# shield_passage_vitesse.net
KiCad netlist of a schematic drawn in EAGLE
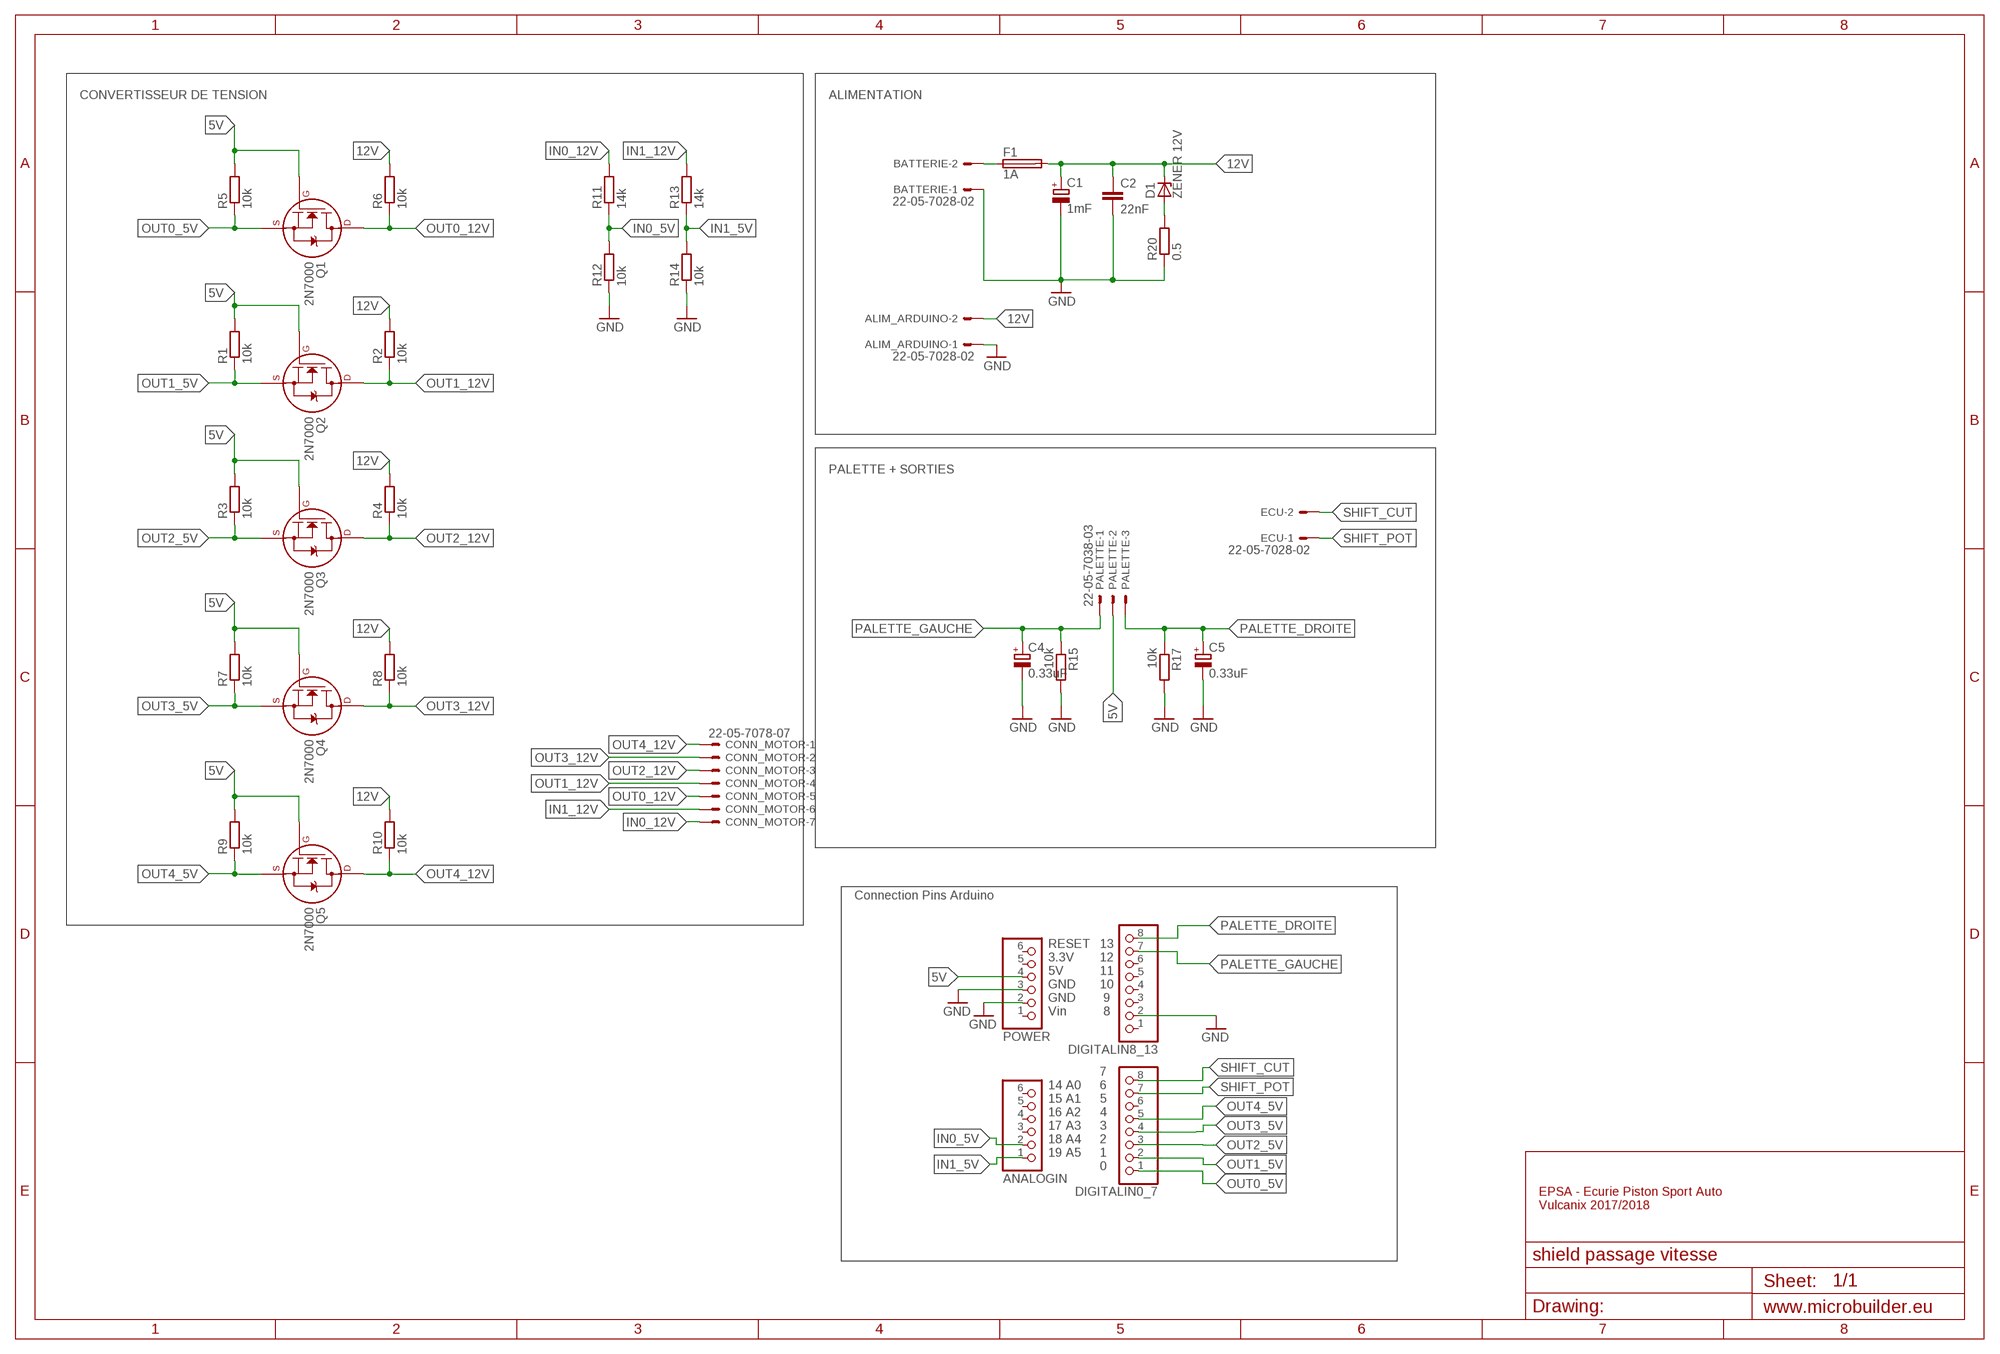
[diagram p0: schematic, sheet 1]

(export (version "E")
  (design (tool "Eeschema 10.0.6"))
  (components
    (comp (ref "ALIM_ARDUINO")
      (value "22-05-7028-02")
      (footprint "eagle-import:7395-02")
      (libsource (lib "eagle-import") (part "22-?-0205-7028"))
    )
    (comp (ref "ANALOGIN")
      (value "PINHD-1X6CB")
      (footprint "eagle-import:1X06-CLEANBIG")
      (libsource (lib "eagle-import") (part "PINHD-1X6CB"))
    )
    (comp (ref "BATTERIE")
      (value "22-05-7028-02")
      (footprint "eagle-import:7395-02")
      (libsource (lib "eagle-import") (part "22-?-0205-7028"))
    )
    (comp (ref "C1")
      (value "1mF")
      (footprint "eagle-import:E7,5-16")
      (libsource (lib "eagle-import") (part "rcl_334_CPOL-EUE7.5-16"))
    )
    (comp (ref "C2")
      (value "22nF")
      (footprint "eagle-import:C025-025X050")
      (libsource (lib "eagle-import") (part "C-EU025-025X050"))
    )
    (comp (ref "C4")
      (value "0.33uF")
      (footprint "eagle-import:E2,5-6E")
      (libsource (lib "eagle-import") (part "CPOL-EUE2,5-6E"))
    )
    (comp (ref "C5")
      (value "0.33uF")
      (footprint "eagle-import:E2,5-6E")
      (libsource (lib "eagle-import") (part "CPOL-EUE2,5-6E"))
    )
    (comp (ref "CONN_MOTOR")
      (value "22-05-7078-07")
      (footprint "eagle-import:7395-07")
      (libsource (lib "eagle-import") (part "22-?-0705-7078"))
    )
    (comp (ref "D1")
      (value "ZENER 12V")
      (footprint "eagle-import:DO41Z10")
      (libsource (lib "eagle-import") (part "ZENER-DIODEDO41Z10"))
    )
    (comp (ref "DIGITALIN0_7")
      (value "PINHD-1X8CLEANBIG")
      (footprint "eagle-import:1X08-CLEANBIG")
      (libsource (lib "eagle-import") (part "PINHD-1X8CLEANBIG"))
    )
    (comp (ref "DIGITALIN8_13")
      (value "PINHD-1X8CLEANBIG")
      (footprint "eagle-import:1X08-CLEANBIG")
      (libsource (lib "eagle-import") (part "PINHD-1X8CLEANBIG"))
    )
    (comp (ref "ECU")
      (value "22-05-7028-02")
      (footprint "eagle-import:7395-02")
      (libsource (lib "eagle-import") (part "22-?-0205-7028"))
    )
    (comp (ref "F1")
      (value "1A")
      (footprint "eagle-import:SH25")
      (fields (field (name "MF") "SCHURTER") (field (name "MPN") "0031.8211"))
      (libsource (lib "eagle-import") (part "SH25"))
    )
    (comp (ref "PALETTE")
      (value "22-05-7038-03")
      (footprint "eagle-import:7395-03")
      (libsource (lib "eagle-import") (part "22-?-0305-7038"))
    )
    (comp (ref "POWER")
      (value "PINHD-1X6CB")
      (footprint "eagle-import:1X06-CLEANBIG")
      (libsource (lib "eagle-import") (part "PINHD-1X6CB"))
    )
    (comp (ref "Q1")
      (value "2N7000")
      (footprint "eagle-import:TO-92")
      (libsource (lib "eagle-import") (part "2N700_TO920"))
    )
    (comp (ref "Q2")
      (value "2N7000")
      (footprint "eagle-import:TO-92")
      (libsource (lib "eagle-import") (part "2N700_TO920"))
    )
    (comp (ref "Q3")
      (value "2N7000")
      (footprint "eagle-import:TO-92")
      (libsource (lib "eagle-import") (part "2N700_TO920"))
    )
    (comp (ref "Q4")
      (value "2N7000")
      (footprint "eagle-import:TO-92")
      (libsource (lib "eagle-import") (part "2N700_TO920"))
    )
    (comp (ref "Q5")
      (value "2N7000")
      (footprint "eagle-import:TO-92")
      (libsource (lib "eagle-import") (part "2N700_TO920"))
    )
    (comp (ref "R1")
      (value "10k")
      (footprint "eagle-import:0204_7")
      (libsource (lib "eagle-import") (part "R-EU_0204/7"))
    )
    (comp (ref "R2")
      (value "10k")
      (footprint "eagle-import:0204_7")
      (libsource (lib "eagle-import") (part "R-EU_0204/7"))
    )
    (comp (ref "R3")
      (value "10k")
      (footprint "eagle-import:0204_7")
      (libsource (lib "eagle-import") (part "R-EU_0204/7"))
    )
    (comp (ref "R4")
      (value "10k")
      (footprint "eagle-import:0204_7")
      (libsource (lib "eagle-import") (part "R-EU_0204/7"))
    )
    (comp (ref "R5")
      (value "10k")
      (footprint "eagle-import:0204_7")
      (libsource (lib "eagle-import") (part "R-EU_0204/7"))
    )
    (comp (ref "R6")
      (value "10k")
      (footprint "eagle-import:0204_7")
      (libsource (lib "eagle-import") (part "R-EU_0204/7"))
    )
    (comp (ref "R7")
      (value "10k")
      (footprint "eagle-import:0204_7")
      (libsource (lib "eagle-import") (part "R-EU_0204/7"))
    )
    (comp (ref "R8")
      (value "10k")
      (footprint "eagle-import:0204_7")
      (libsource (lib "eagle-import") (part "R-EU_0204/7"))
    )
    (comp (ref "R9")
      (value "10k")
      (footprint "eagle-import:0204_7")
      (libsource (lib "eagle-import") (part "R-EU_0204/7"))
    )
    (comp (ref "R10")
      (value "10k")
      (footprint "eagle-import:0204_7")
      (libsource (lib "eagle-import") (part "R-EU_0204/7"))
    )
    (comp (ref "R11")
      (value "14k")
      (footprint "eagle-import:0204_7")
      (libsource (lib "eagle-import") (part "R-EU_0204/7"))
    )
    (comp (ref "R12")
      (value "10k")
      (footprint "eagle-import:0204_7")
      (libsource (lib "eagle-import") (part "R-EU_0204/7"))
    )
    (comp (ref "R13")
      (value "14k")
      (footprint "eagle-import:0204_7")
      (libsource (lib "eagle-import") (part "R-EU_0204/7"))
    )
    (comp (ref "R14")
      (value "10k")
      (footprint "eagle-import:0204_7")
      (libsource (lib "eagle-import") (part "R-EU_0204/7"))
    )
    (comp (ref "R15")
      (value "10k")
      (footprint "eagle-import:0204_7")
      (libsource (lib "eagle-import") (part "R-EU_0204/7"))
    )
    (comp (ref "R17")
      (value "10k")
      (footprint "eagle-import:0204_7")
      (libsource (lib "eagle-import") (part "R-EU_0204/7"))
    )
    (comp (ref "R20")
      (value "0.5")
      (footprint "eagle-import:0309_12")
      (libsource (lib "eagle-import") (part "R-EU_0309/12"))
    )
  )
  (nets
    (net (code "1") (name "5V") (class "Default")
      (node (ref "PALETTE") (pin "2") (pinfunction "S_2") (pintype "passive"))
      (node (ref "POWER") (pin "4") (pinfunction "4_4") (pintype "passive"))
      (node (ref "Q1") (pin "2") (pinfunction "G_2") (pintype "tri_state"))
      (node (ref "Q2") (pin "2") (pinfunction "G_2") (pintype "tri_state"))
      (node (ref "Q3") (pin "2") (pinfunction "G_2") (pintype "tri_state"))
      (node (ref "Q4") (pin "2") (pinfunction "G_2") (pintype "tri_state"))
      (node (ref "Q5") (pin "2") (pinfunction "G_2") (pintype "tri_state"))
      (node (ref "R1") (pin "2") (pinfunction "2_2") (pintype "passive"))
      (node (ref "R3") (pin "2") (pinfunction "2_2") (pintype "passive"))
      (node (ref "R5") (pin "2") (pinfunction "2_2") (pintype "passive"))
      (node (ref "R7") (pin "2") (pinfunction "2_2") (pintype "passive"))
      (node (ref "R9") (pin "2") (pinfunction "2_2") (pintype "passive"))
    )
    (net (code "2") (name "12V") (class "Default")
      (node (ref "ALIM_ARDUINO") (pin "2") (pinfunction "S_2") (pintype "passive"))
      (node (ref "C1") (pin "+") (pinfunction "+_+") (pintype "passive"))
      (node (ref "C2") (pin "1") (pinfunction "1_1") (pintype "passive"))
      (node (ref "D1") (pin "C") (pinfunction "C_C") (pintype "passive"))
      (node (ref "F1") (pin "2") (pinfunction "2_2") (pintype "passive"))
      (node (ref "R10") (pin "2") (pinfunction "2_2") (pintype "passive"))
      (node (ref "R2") (pin "2") (pinfunction "2_2") (pintype "passive"))
      (node (ref "R4") (pin "2") (pinfunction "2_2") (pintype "passive"))
      (node (ref "R6") (pin "2") (pinfunction "2_2") (pintype "passive"))
      (node (ref "R8") (pin "2") (pinfunction "2_2") (pintype "passive"))
    )
    (net (code "3") (name "GND") (class "Default")
      (node (ref "ALIM_ARDUINO") (pin "1") (pinfunction "S_1") (pintype "passive"))
      (node (ref "BATTERIE") (pin "1") (pinfunction "S_1") (pintype "passive"))
      (node (ref "C1") (pin "-") (pinfunction "-_-") (pintype "passive"))
      (node (ref "C2") (pin "2") (pinfunction "2_2") (pintype "passive"))
      (node (ref "C4") (pin "-") (pinfunction "-_-") (pintype "passive"))
      (node (ref "C5") (pin "-") (pinfunction "-_-") (pintype "passive"))
      (node (ref "DIGITALIN8_13") (pin "2") (pinfunction "2_2") (pintype "passive"))
      (node (ref "POWER") (pin "2") (pinfunction "2_2") (pintype "passive"))
      (node (ref "POWER") (pin "3") (pinfunction "3_3") (pintype "passive"))
      (node (ref "R12") (pin "1") (pinfunction "1_1") (pintype "passive"))
      (node (ref "R14") (pin "1") (pinfunction "1_1") (pintype "passive"))
      (node (ref "R15") (pin "2") (pinfunction "2_2") (pintype "passive"))
      (node (ref "R17") (pin "2") (pinfunction "2_2") (pintype "passive"))
      (node (ref "R20") (pin "1") (pinfunction "1_1") (pintype "passive"))
    )
    (net (code "4") (name "IN0_5V") (class "Default")
      (node (ref "ANALOGIN") (pin "2") (pinfunction "2_2") (pintype "passive"))
      (node (ref "R11") (pin "1") (pinfunction "1_1") (pintype "passive"))
      (node (ref "R12") (pin "2") (pinfunction "2_2") (pintype "passive"))
    )
    (net (code "5") (name "IN0_12V") (class "Default")
      (node (ref "CONN_MOTOR") (pin "7") (pinfunction "S_7") (pintype "passive"))
      (node (ref "R11") (pin "2") (pinfunction "2_2") (pintype "passive"))
    )
    (net (code "6") (name "IN1_5V") (class "Default")
      (node (ref "ANALOGIN") (pin "1") (pinfunction "1_1") (pintype "passive"))
      (node (ref "R13") (pin "1") (pinfunction "1_1") (pintype "passive"))
      (node (ref "R14") (pin "2") (pinfunction "2_2") (pintype "passive"))
    )
    (net (code "7") (name "IN1_12V") (class "Default")
      (node (ref "CONN_MOTOR") (pin "6") (pinfunction "S_6") (pintype "passive"))
      (node (ref "R13") (pin "2") (pinfunction "2_2") (pintype "passive"))
    )
    (net (code "8") (name "Net-(BATTERIEB-S)") (class "Default")
      (node (ref "BATTERIE") (pin "2") (pinfunction "S_2") (pintype "passive"))
      (node (ref "F1") (pin "1") (pinfunction "1_1") (pintype "passive"))
    )
    (net (code "9") (name "Net-(D1-PadA)") (class "Default")
      (node (ref "D1") (pin "A") (pinfunction "A_A") (pintype "passive"))
      (node (ref "R20") (pin "2") (pinfunction "2_2") (pintype "passive"))
    )
    (net (code "10") (name "OUT0_5V") (class "Default")
      (node (ref "DIGITALIN0_7") (pin "1") (pinfunction "1_1") (pintype "passive"))
      (node (ref "Q1") (pin "1") (pinfunction "S_1") (pintype "bidirectional"))
      (node (ref "R5") (pin "1") (pinfunction "1_1") (pintype "passive"))
    )
    (net (code "11") (name "OUT0_12V") (class "Default")
      (node (ref "CONN_MOTOR") (pin "5") (pinfunction "S_5") (pintype "passive"))
      (node (ref "Q1") (pin "3") (pinfunction "D_3") (pintype "bidirectional"))
      (node (ref "R6") (pin "1") (pinfunction "1_1") (pintype "passive"))
    )
    (net (code "12") (name "OUT1_5V") (class "Default")
      (node (ref "DIGITALIN0_7") (pin "2") (pinfunction "2_2") (pintype "passive"))
      (node (ref "Q2") (pin "1") (pinfunction "S_1") (pintype "bidirectional"))
      (node (ref "R1") (pin "1") (pinfunction "1_1") (pintype "passive"))
    )
    (net (code "13") (name "OUT1_12V") (class "Default")
      (node (ref "CONN_MOTOR") (pin "4") (pinfunction "S_4") (pintype "passive"))
      (node (ref "Q2") (pin "3") (pinfunction "D_3") (pintype "bidirectional"))
      (node (ref "R2") (pin "1") (pinfunction "1_1") (pintype "passive"))
    )
    (net (code "14") (name "OUT2_5V") (class "Default")
      (node (ref "DIGITALIN0_7") (pin "3") (pinfunction "3_3") (pintype "passive"))
      (node (ref "Q3") (pin "1") (pinfunction "S_1") (pintype "bidirectional"))
      (node (ref "R3") (pin "1") (pinfunction "1_1") (pintype "passive"))
    )
    (net (code "15") (name "OUT2_12V") (class "Default")
      (node (ref "CONN_MOTOR") (pin "3") (pinfunction "S_3") (pintype "passive"))
      (node (ref "Q3") (pin "3") (pinfunction "D_3") (pintype "bidirectional"))
      (node (ref "R4") (pin "1") (pinfunction "1_1") (pintype "passive"))
    )
    (net (code "16") (name "OUT3_5V") (class "Default")
      (node (ref "DIGITALIN0_7") (pin "4") (pinfunction "4_4") (pintype "passive"))
      (node (ref "Q4") (pin "1") (pinfunction "S_1") (pintype "bidirectional"))
      (node (ref "R7") (pin "1") (pinfunction "1_1") (pintype "passive"))
    )
    (net (code "17") (name "OUT3_12V") (class "Default")
      (node (ref "CONN_MOTOR") (pin "2") (pinfunction "S_2") (pintype "passive"))
      (node (ref "Q4") (pin "3") (pinfunction "D_3") (pintype "bidirectional"))
      (node (ref "R8") (pin "1") (pinfunction "1_1") (pintype "passive"))
    )
    (net (code "18") (name "OUT4_5V") (class "Default")
      (node (ref "DIGITALIN0_7") (pin "5") (pinfunction "5_5") (pintype "passive"))
      (node (ref "Q5") (pin "1") (pinfunction "S_1") (pintype "bidirectional"))
      (node (ref "R9") (pin "1") (pinfunction "1_1") (pintype "passive"))
    )
    (net (code "19") (name "OUT4_12V") (class "Default")
      (node (ref "CONN_MOTOR") (pin "1") (pinfunction "S_1") (pintype "passive"))
      (node (ref "Q5") (pin "3") (pinfunction "D_3") (pintype "bidirectional"))
      (node (ref "R10") (pin "1") (pinfunction "1_1") (pintype "passive"))
    )
    (net (code "20") (name "PALETTE_DROITE") (class "Default")
      (node (ref "C5") (pin "+") (pinfunction "+_+") (pintype "passive"))
      (node (ref "DIGITALIN8_13") (pin "8") (pinfunction "8_8") (pintype "passive"))
      (node (ref "PALETTE") (pin "3") (pinfunction "S_3") (pintype "passive"))
      (node (ref "R17") (pin "1") (pinfunction "1_1") (pintype "passive"))
    )
    (net (code "21") (name "PALETTE_GAUCHE") (class "Default")
      (node (ref "C4") (pin "+") (pinfunction "+_+") (pintype "passive"))
      (node (ref "DIGITALIN8_13") (pin "7") (pinfunction "7_7") (pintype "passive"))
      (node (ref "PALETTE") (pin "1") (pinfunction "S_1") (pintype "passive"))
      (node (ref "R15") (pin "1") (pinfunction "1_1") (pintype "passive"))
    )
    (net (code "22") (name "SHIFT_CUT") (class "Default")
      (node (ref "DIGITALIN0_7") (pin "8") (pinfunction "8_8") (pintype "passive"))
      (node (ref "ECU") (pin "2") (pinfunction "S_2") (pintype "passive"))
    )
    (net (code "23") (name "SHIFT_POT") (class "Default")
      (node (ref "DIGITALIN0_7") (pin "7") (pinfunction "7_7") (pintype "passive"))
      (node (ref "ECU") (pin "1") (pinfunction "S_1") (pintype "passive"))
    )
    (net (code "24") (name "unconnected-(ANALOGIN-Pad3)") (class "Default")
      (node (ref "ANALOGIN") (pin "3") (pinfunction "3_3") (pintype "passive"))
    )
    (net (code "25") (name "unconnected-(ANALOGIN-Pad4)") (class "Default")
      (node (ref "ANALOGIN") (pin "4") (pinfunction "4_4") (pintype "passive"))
    )
    (net (code "26") (name "unconnected-(ANALOGIN-Pad5)") (class "Default")
      (node (ref "ANALOGIN") (pin "5") (pinfunction "5_5") (pintype "passive"))
    )
    (net (code "27") (name "unconnected-(ANALOGIN-Pad6)") (class "Default")
      (node (ref "ANALOGIN") (pin "6") (pinfunction "6_6") (pintype "passive"))
    )
    (net (code "28") (name "unconnected-(DIGITALIN0_7-Pad6)") (class "Default")
      (node (ref "DIGITALIN0_7") (pin "6") (pinfunction "6_6") (pintype "passive"))
    )
    (net (code "29") (name "unconnected-(DIGITALIN8_13-Pad1)") (class "Default")
      (node (ref "DIGITALIN8_13") (pin "1") (pinfunction "1_1") (pintype "passive"))
    )
    (net (code "30") (name "unconnected-(DIGITALIN8_13-Pad3)") (class "Default")
      (node (ref "DIGITALIN8_13") (pin "3") (pinfunction "3_3") (pintype "passive"))
    )
    (net (code "31") (name "unconnected-(DIGITALIN8_13-Pad4)") (class "Default")
      (node (ref "DIGITALIN8_13") (pin "4") (pinfunction "4_4") (pintype "passive"))
    )
    (net (code "32") (name "unconnected-(DIGITALIN8_13-Pad5)") (class "Default")
      (node (ref "DIGITALIN8_13") (pin "5") (pinfunction "5_5") (pintype "passive"))
    )
    (net (code "33") (name "unconnected-(DIGITALIN8_13-Pad6)") (class "Default")
      (node (ref "DIGITALIN8_13") (pin "6") (pinfunction "6_6") (pintype "passive"))
    )
    (net (code "34") (name "unconnected-(POWER-Pad1)") (class "Default")
      (node (ref "POWER") (pin "1") (pinfunction "1_1") (pintype "passive"))
    )
    (net (code "35") (name "unconnected-(POWER-Pad5)") (class "Default")
      (node (ref "POWER") (pin "5") (pinfunction "5_5") (pintype "passive"))
    )
    (net (code "36") (name "unconnected-(POWER-Pad6)") (class "Default")
      (node (ref "POWER") (pin "6") (pinfunction "6_6") (pintype "passive"))
    )
  )
)
